# Single_12V.net
KiCad netlist of a schematic drawn in Altium Designer
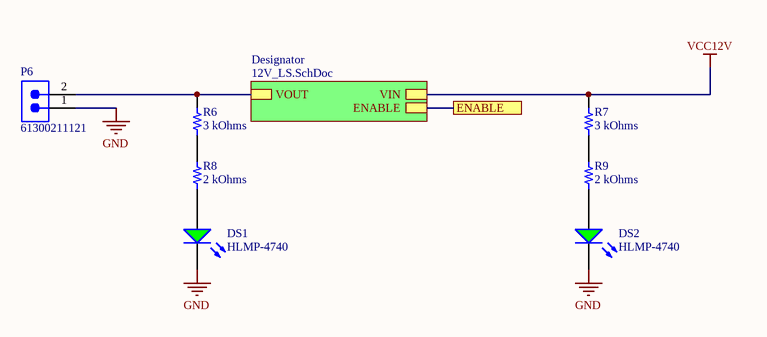
[diagram p0: Single_12V.SchDoc]

(export (version "E")
  (design (tool "Eeschema 10.0.6"))
  (components
    (comp (ref "DS1")
      (value "HLMP-4740")
      (footprint "AVAG-HLMP-4740")
      (description "T-1 3/4 (5 mm) Low Current LED Lamp, Green, 1.9 V, -20 to 100 degC, 2-Pin THD, RoHS, Bulk")
      (fields (field (name "MANUFACTURER") "AvagoTechnologies"))
      (libsource (lib "Altium Content Vault") (part "LED-GREEN-AK-2"))
    )
    (comp (ref "DS2")
      (value "HLMP-4740")
      (footprint "AVAG-HLMP-4740")
      (description "T-1 3/4 (5 mm) Low Current LED Lamp, Green, 1.9 V, -20 to 100 degC, 2-Pin THD, RoHS, Bulk")
      (fields (field (name "MANUFACTURER") "AvagoTechnologies"))
      (libsource (lib "Altium Content Vault") (part "LED-GREEN-AK-2"))
    )
    (comp (ref "P6")
      (value "61300211121")
      (footprint "61300211121")
      (libsource (lib "Altium Content Vault") (part "Header_Male_1R_02P"))
    )
    (comp (ref "R6")
      (value "3 kOhms")
      (footprint "RES 0805_2012")
      (description "RES SMD 3K OHM 0.5% 1/8W 0805")
      (fields (field (name "PART NUMBER") "RT0805DRD073KL") (field (name "MANUFACTURER") "Yageo"))
      (libsource (lib "Celestial Altium Library - altium_library") (part "Resistor"))
    )
    (comp (ref "R7")
      (value "3 kOhms")
      (footprint "RES 0805_2012")
      (description "RES SMD 3K OHM 0.5% 1/8W 0805")
      (fields (field (name "PART NUMBER") "RT0805DRD073KL") (field (name "MANUFACTURER") "Yageo"))
      (libsource (lib "Celestial Altium Library - altium_library") (part "Resistor"))
    )
    (comp (ref "R8")
      (value "2 kOhms")
      (footprint "RES 0805_2012")
      (description "RES SMD 2K OHM 1% 1/2W 0805")
      (fields (field (name "PART NUMBER") "RCS08052K00FKEA") (field (name "MANUFACTURER") "Vishay Dale"))
      (libsource (lib "Celestial Altium Library - altium_library") (part "Resistor"))
    )
    (comp (ref "R9")
      (value "2 kOhms")
      (footprint "RES 0805_2012")
      (description "RES SMD 2K OHM 1% 1/2W 0805")
      (fields (field (name "PART NUMBER") "RCS08052K00FKEA") (field (name "MANUFACTURER") "Vishay Dale"))
      (libsource (lib "Celestial Altium Library - altium_library") (part "Resistor"))
    )
  )
  (nets
    (net (code "2") (name "/VOUT") (class "Default")
      (node (ref "P6") (pin "2") (pinfunction "2_2") (pintype "passive"))
      (node (ref "R6") (pin "2") (pinfunction "2_2") (pintype "passive"))
    )
    (net (code "3") (name "GND") (class "Default")
      (node (ref "DS1") (pin "2") (pinfunction "K_2") (pintype "passive"))
      (node (ref "DS2") (pin "2") (pinfunction "K_2") (pintype "passive"))
      (node (ref "P6") (pin "1") (pinfunction "1_1") (pintype "passive"))
    )
    (net (code "4") (name "Net-(DS1-A)") (class "Default")
      (node (ref "DS1") (pin "1") (pinfunction "A_1") (pintype "passive"))
      (node (ref "R8") (pin "1") (pinfunction "1_1") (pintype "passive"))
    )
    (net (code "5") (name "Net-(DS2-A)") (class "Default")
      (node (ref "DS2") (pin "1") (pinfunction "A_1") (pintype "passive"))
      (node (ref "R9") (pin "1") (pinfunction "1_1") (pintype "passive"))
    )
    (net (code "6") (name "Net-(R6-Pad1)") (class "Default")
      (node (ref "R6") (pin "1") (pinfunction "1_1") (pintype "passive"))
      (node (ref "R8") (pin "2") (pinfunction "2_2") (pintype "passive"))
    )
    (net (code "7") (name "Net-(R7-Pad1)") (class "Default")
      (node (ref "R7") (pin "1") (pinfunction "1_1") (pintype "passive"))
      (node (ref "R9") (pin "2") (pinfunction "2_2") (pintype "passive"))
    )
    (net (code "8") (name "VCC12V") (class "Default")
      (node (ref "R7") (pin "2") (pinfunction "2_2") (pintype "passive"))
    )
  )
)
